# Controller_Sheet.net
KiCad netlist of a schematic drawn in Altium Designer
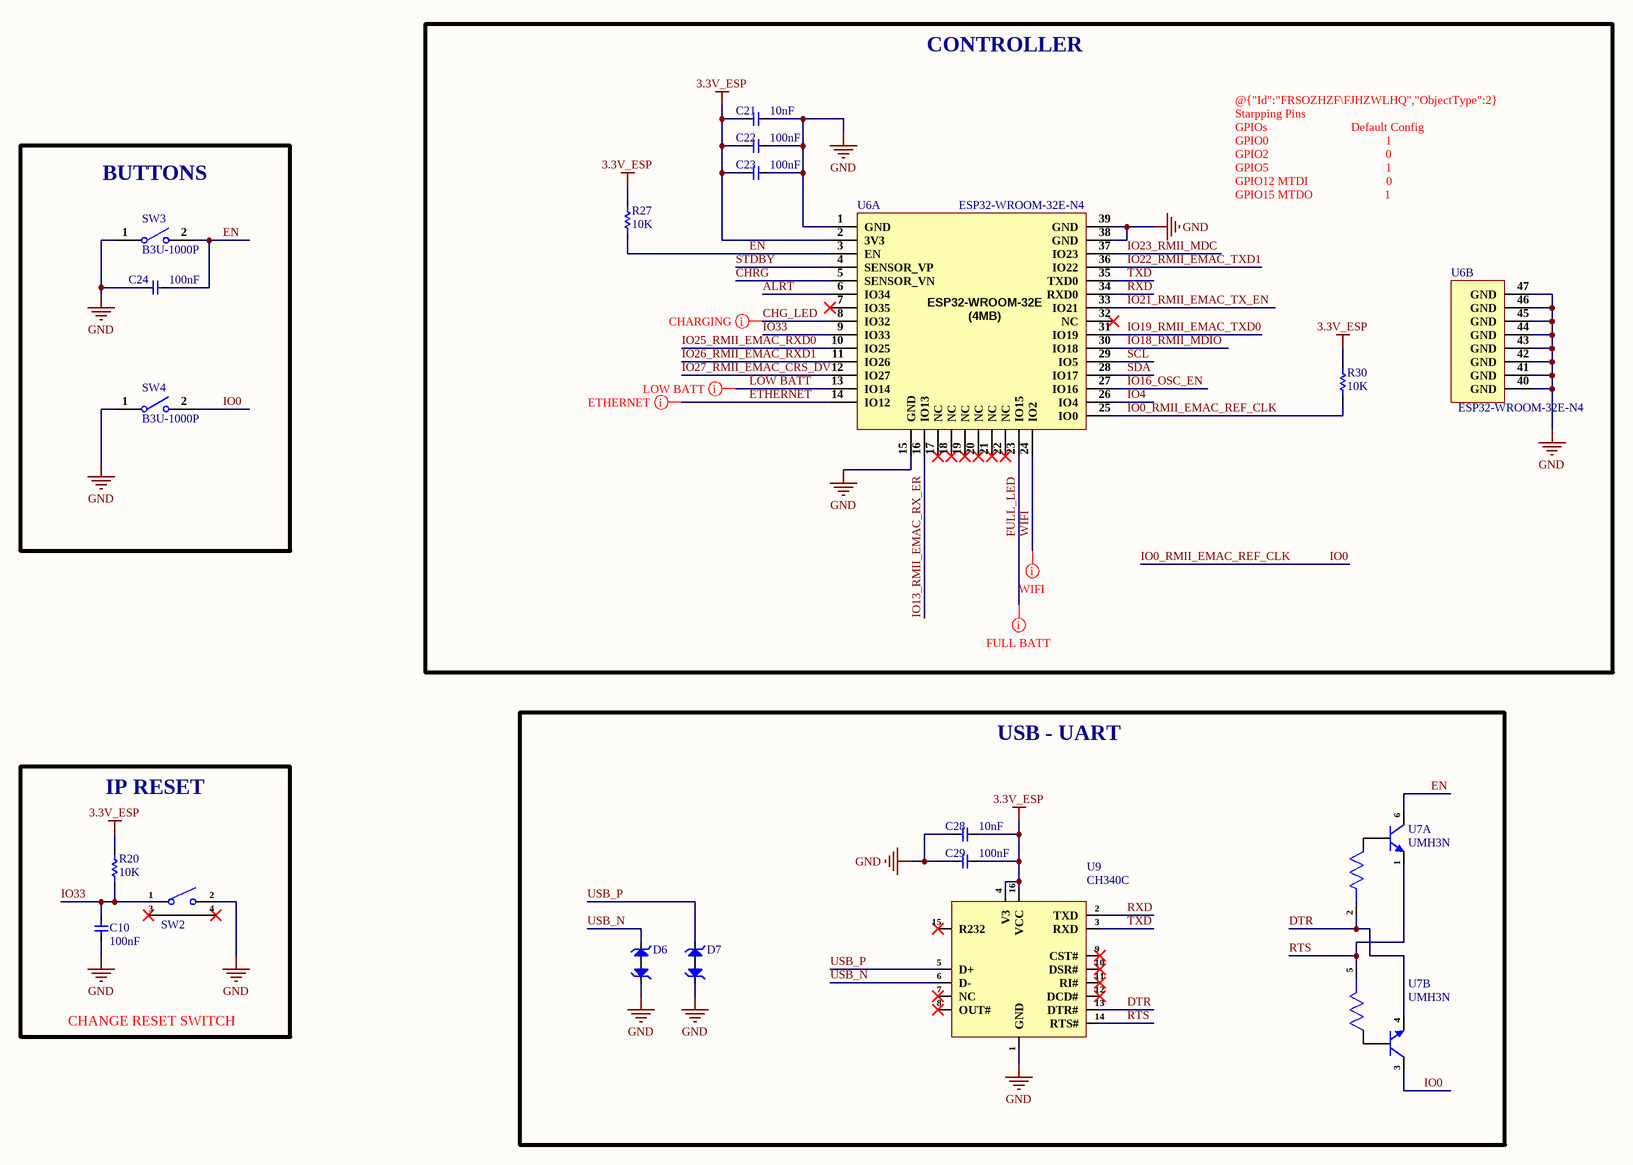
[diagram p0: Controller_Sheet.SchDoc]

(export (version "E")
  (design (tool "Eeschema 10.0.6"))
  (components
    (comp (ref "C10")
      (value "100nF")
      (footprint "cap-0402")
      (description "CAP CER 0.1UF 50V X7R 0402")
      (fields
        (field (name "MANUFACTURER") "TDK")
        (field (name "MANUFACTURER PART NUMBER") "C1005X7R1H104KT000F")
      )
      (libsource (lib "eSpark Libraries") (part "C1005X7R1H104KT000F"))
    )
    (comp (ref "C21")
      (value "10nF")
      (footprint "Cap-0402")
      (description "CAP CER 10000PF 25V X7R 0402")
      (fields
        (field (name "MANUFACTURER") "Yageo")
        (field (name "MANUFACTURER PART NUMBER") "CC0402KRX7R8BB103")
      )
      (libsource (lib "eSpark Libraries") (part "CC0402KRX7R8BB103"))
    )
    (comp (ref "C22")
      (value "100nF")
      (footprint "cap-0402")
      (description "CAP CER 0.1UF 50V X7R 0402")
      (fields
        (field (name "MANUFACTURER") "TDK")
        (field (name "MANUFACTURER PART NUMBER") "C1005X7R1H104KT000F")
      )
      (libsource (lib "eSpark Libraries") (part "C1005X7R1H104KT000F"))
    )
    (comp (ref "C23")
      (value "100nF")
      (footprint "cap-0402")
      (description "CAP CER 0.1UF 50V X7R 0402")
      (fields
        (field (name "MANUFACTURER") "TDK")
        (field (name "MANUFACTURER PART NUMBER") "C1005X7R1H104KT000F")
      )
      (libsource (lib "eSpark Libraries") (part "C1005X7R1H104KT000F"))
    )
    (comp (ref "C24")
      (value "100nF")
      (footprint "cap-0402")
      (description "CAP CER 0.1UF 50V X7R 0402")
      (fields
        (field (name "MANUFACTURER") "TDK")
        (field (name "MANUFACTURER PART NUMBER") "C1005X7R1H104KT000F")
      )
      (libsource (lib "eSpark Libraries") (part "C1005X7R1H104KT000F"))
    )
    (comp (ref "C28")
      (value "10nF")
      (footprint "Cap-0402")
      (description "CAP CER 10000PF 25V X7R 0402")
      (fields
        (field (name "MANUFACTURER") "Yageo")
        (field (name "MANUFACTURER PART NUMBER") "CC0402KRX7R8BB103")
      )
      (libsource (lib "eSpark Libraries") (part "CC0402KRX7R8BB103"))
    )
    (comp (ref "C29")
      (value "100nF")
      (footprint "cap-0402")
      (description "CAP CER 0.1UF 50V X7R 0402")
      (fields
        (field (name "MANUFACTURER") "TDK")
        (field (name "MANUFACTURER PART NUMBER") "C1005X7R1H104KT000F")
      )
      (libsource (lib "eSpark Libraries") (part "C1005X7R1H104KT000F"))
    )
    (comp (ref "D6")
      (value "PESD5V0H1BSFYL")
      (footprint "DSN0603-2")
      (description "TVS DIODE 5VWM 6.3VC DSN0603-2")
      (fields (field (name "MANUFACTURER") "Nexperia") (field (name "LCSC PART NUMBER") "C477989"))
      (libsource (lib "eSpark Libraries") (part "PESD5V0H1BSFYL"))
    )
    (comp (ref "D7")
      (value "PESD5V0H1BSFYL")
      (footprint "DSN0603-2")
      (description "TVS DIODE 5VWM 6.3VC DSN0603-2")
      (fields (field (name "MANUFACTURER") "Nexperia") (field (name "LCSC PART NUMBER") "C477989"))
      (libsource (lib "eSpark Libraries") (part "PESD5V0H1BSFYL"))
    )
    (comp (ref "R20")
      (value "10K")
      (footprint "Res-0402")
      (description "RES 10K OHM 1% 1/16W 0402")
      (fields
        (field (name "MANUFACTURER") "Yageo")
        (field (name "MANUFACTURER PART NUMBER") "RC0402FR-0710KL")
      )
      (libsource (lib "eSpark Libraries") (part "RC0402FR-0710KL"))
    )
    (comp (ref "R27")
      (value "10K")
      (footprint "Res-0402")
      (description "RES 10K OHM 1% 1/16W 0402")
      (fields
        (field (name "MANUFACTURER") "Yageo")
        (field (name "MANUFACTURER PART NUMBER") "RC0402FR-0710KL")
      )
      (libsource (lib "eSpark Libraries") (part "RC0402FR-0710KL"))
    )
    (comp (ref "R30")
      (value "10K")
      (footprint "Res-0402")
      (description "RES 10K OHM 1% 1/16W 0402")
      (fields
        (field (name "MANUFACTURER") "Yageo")
        (field (name "MANUFACTURER PART NUMBER") "RC0402FR-0710KL")
      )
      (libsource (lib "eSpark Libraries") (part "RC0402FR-0710KL"))
    )
    (comp (ref "SW2")
      (value "1-1825027-4")
      (footprint "1-1825027-4")
      (fields (field (name "MANUFACTURER") "TE Connectivity") (field (name "LCSC PART NUMBER") "C2928195"))
      (libsource (lib "eSpark Libraries") (part "1-1825027-4"))
    )
    (comp (ref "SW3")
      (value "B3U-1000P")
      (footprint "B3U-1000P")
      (description "SWITCH TACTILE SPST-NO 0.05A 12V")
      (fields (field (name "MANUFACTURER") "Omron") (field (name "LCSC PART NUMBER") "C231329"))
      (libsource (lib "eSpark Libraries") (part "B3U-1000P"))
    )
    (comp (ref "SW4")
      (value "B3U-1000P")
      (footprint "B3U-1000P")
      (description "SWITCH TACTILE SPST-NO 0.05A 12V")
      (fields (field (name "MANUFACTURER") "Omron") (field (name "LCSC PART NUMBER") "C231329"))
      (libsource (lib "eSpark Libraries") (part "B3U-1000P"))
    )
    (comp (ref "U6")
      (value "ESP32-WROOM-32E-N4")
      (footprint "38-SMD Module")
      (description "RX TXRX MOD WIFI TRACE ANT SMD")
      (fields (field (name "MANUFACTURER") "Espressif Systems") (field (name "LCSC PART NUMBER") "C701341"))
      (libsource (lib "eSpark Libraries") (part "ESP32-WROOM-32E-N4"))
    )
    (comp (ref "U7")
      (value "UMH3N")
      (footprint "SC-70-6_")
      (description "2 NPN pre-biased (Dual) 150mW 100mA 50V SC-70-6(SOT-363) Digital Transistors ROHS")
      (fields (field (name "MANUFACTURER") "Changjiang") (field (name "LCSC PART NUMBER") "C62892"))
      (libsource (lib "eSpark Libraries") (part "UMH3N"))
    )
    (comp (ref "U9")
      (value "CH340C")
      (footprint "SOP-16")
      (description "2Mbps Transceiver USB 2.0 SOP-16 USB ICs ROHS")
      (fields (field (name "MANUFACTURER") "WCH") (field (name "LCSC PART NUMBER") "C84681"))
      (libsource (lib "eSpark Libraries") (part "CH340C"))
    )
  )
  (nets
    (net (code "1") (name "/ALRT") (class "Default")
      (node (ref "U6") (pin "6") (pinfunction "IO34_6") (pintype "passive"))
    )
    (net (code "2") (name "/CHG_LED") (class "Default")
      (node (ref "U6") (pin "8") (pinfunction "IO32_8") (pintype "passive"))
    )
    (net (code "3") (name "/CHRG") (class "Default")
      (node (ref "U6") (pin "5") (pinfunction "SENSOR_VN_5") (pintype "passive"))
    )
    (net (code "4") (name "/DTR") (class "Default")
      (node (ref "U7") (pin "2") (pintype "passive"))
      (node (ref "U7") (pin "4") (pinfunction "E_4") (pintype "passive"))
      (node (ref "U9") (pin "13") (pinfunction "DTR#_13") (pintype "passive"))
    )
    (net (code "5") (name "/EN") (class "Default")
      (node (ref "C24") (pin "1") (pinfunction "1_1") (pintype "passive"))
      (node (ref "R27") (pin "1") (pinfunction "1_1") (pintype "passive"))
      (node (ref "SW3") (pin "2") (pinfunction "2_2") (pintype "passive"))
      (node (ref "U6") (pin "3") (pinfunction "EN_3") (pintype "passive"))
      (node (ref "U7") (pin "6") (pinfunction "C_6") (pintype "passive"))
    )
    (net (code "6") (name "/ETHERNET") (class "Default")
      (node (ref "U6") (pin "14") (pinfunction "IO12_14") (pintype "passive"))
    )
    (net (code "7") (name "/FULL_LED") (class "Default")
      (node (ref "U6") (pin "23") (pinfunction "IO15_23") (pintype "passive"))
    )
    (net (code "8") (name "/IO0") (class "Default")
      (node (ref "R30") (pin "1") (pinfunction "1_1") (pintype "passive"))
      (node (ref "SW4") (pin "2") (pinfunction "2_2") (pintype "passive"))
      (node (ref "U6") (pin "25") (pinfunction "IO0_25") (pintype "passive"))
      (node (ref "U7") (pin "3") (pinfunction "C_3") (pintype "passive"))
    )
    (net (code "9") (name "/IO4") (class "Default")
      (node (ref "U6") (pin "26") (pinfunction "IO4_26") (pintype "passive"))
    )
    (net (code "10") (name "/IO13_RMII_EMAC_RX_ER") (class "Default")
      (node (ref "U6") (pin "16") (pinfunction "IO13_16") (pintype "passive"))
    )
    (net (code "11") (name "/IO16_OSC_EN") (class "Default")
      (node (ref "U6") (pin "27") (pinfunction "IO16_27") (pintype "passive"))
    )
    (net (code "12") (name "/IO18_RMII_MDIO") (class "Default")
      (node (ref "U6") (pin "30") (pinfunction "IO18_30") (pintype "passive"))
    )
    (net (code "13") (name "/IO19_RMII_EMAC_TXD0") (class "Default")
      (node (ref "U6") (pin "31") (pinfunction "IO19_31") (pintype "passive"))
    )
    (net (code "14") (name "/IO21_RMII_EMAC_TX_EN") (class "Default")
      (node (ref "U6") (pin "33") (pinfunction "IO21_33") (pintype "passive"))
    )
    (net (code "15") (name "/IO22_RMII_EMAC_TXD1") (class "Default")
      (node (ref "U6") (pin "36") (pinfunction "IO22_36") (pintype "passive"))
    )
    (net (code "16") (name "/IO23_RMII_MDC") (class "Default")
      (node (ref "U6") (pin "37") (pinfunction "IO23_37") (pintype "passive"))
    )
    (net (code "17") (name "/IO25_RMII_EMAC_RXD0") (class "Default")
      (node (ref "U6") (pin "10") (pinfunction "IO25_10") (pintype "passive"))
    )
    (net (code "18") (name "/IO26_RMII_EMAC_RXD1") (class "Default")
      (node (ref "U6") (pin "11") (pinfunction "IO26_11") (pintype "passive"))
    )
    (net (code "19") (name "/IO27_RMII_EMAC_CRS_DV") (class "Default")
      (node (ref "U6") (pin "12") (pinfunction "IO27_12") (pintype "passive"))
    )
    (net (code "20") (name "/IO33") (class "Default")
      (node (ref "C10") (pin "1") (pinfunction "1_1") (pintype "passive"))
      (node (ref "R20") (pin "1") (pinfunction "1_1") (pintype "passive"))
      (node (ref "SW2") (pin "1") (pinfunction "2_1") (pintype "passive"))
      (node (ref "U6") (pin "9") (pinfunction "IO33_9") (pintype "passive"))
    )
    (net (code "21") (name "/LOW BATT") (class "Default")
      (node (ref "U6") (pin "13") (pinfunction "IO14_13") (pintype "passive"))
    )
    (net (code "22") (name "/RTS") (class "Default")
      (node (ref "U7") (pin "1") (pinfunction "E_1") (pintype "passive"))
      (node (ref "U7") (pin "5") (pintype "passive"))
      (node (ref "U9") (pin "14") (pinfunction "RTS#_14") (pintype "passive"))
    )
    (net (code "23") (name "/RXD") (class "Default")
      (node (ref "U6") (pin "34") (pinfunction "RXD0_34") (pintype "passive"))
      (node (ref "U9") (pin "2") (pinfunction "TXD_2") (pintype "passive"))
    )
    (net (code "24") (name "/SCL") (class "Default")
      (node (ref "U6") (pin "29") (pinfunction "IO5_29") (pintype "passive"))
    )
    (net (code "25") (name "/SDA") (class "Default")
      (node (ref "U6") (pin "28") (pinfunction "IO17_28") (pintype "passive"))
    )
    (net (code "26") (name "/STDBY") (class "Default")
      (node (ref "U6") (pin "4") (pinfunction "SENSOR_VP_4") (pintype "passive"))
    )
    (net (code "27") (name "/TXD") (class "Default")
      (node (ref "U6") (pin "35") (pinfunction "TXD0_35") (pintype "passive"))
      (node (ref "U9") (pin "3") (pinfunction "RXD_3") (pintype "passive"))
    )
    (net (code "28") (name "/USB_N") (class "Default")
      (node (ref "D6") (pin "2") (pinfunction "2_2") (pintype "passive"))
      (node (ref "U9") (pin "6") (pinfunction "D-_6") (pintype "passive"))
    )
    (net (code "29") (name "/USB_P") (class "Default")
      (node (ref "D7") (pin "2") (pinfunction "2_2") (pintype "passive"))
      (node (ref "U9") (pin "5") (pinfunction "D+_5") (pintype "passive"))
    )
    (net (code "30") (name "/WIFI") (class "Default")
      (node (ref "U6") (pin "24") (pinfunction "IO2_24") (pintype "passive"))
    )
    (net (code "31") (name "3.3V_ESP") (class "Default")
      (node (ref "C21") (pin "2") (pinfunction "2_2") (pintype "passive"))
      (node (ref "C22") (pin "2") (pinfunction "2_2") (pintype "passive"))
      (node (ref "C23") (pin "2") (pinfunction "2_2") (pintype "passive"))
      (node (ref "C28") (pin "1") (pinfunction "1_1") (pintype "passive"))
      (node (ref "C29") (pin "1") (pinfunction "1_1") (pintype "passive"))
      (node (ref "R20") (pin "2") (pinfunction "2_2") (pintype "passive"))
      (node (ref "R27") (pin "2") (pinfunction "2_2") (pintype "passive"))
      (node (ref "R30") (pin "2") (pinfunction "2_2") (pintype "passive"))
      (node (ref "U6") (pin "2") (pinfunction "3V3_2") (pintype "passive"))
      (node (ref "U9") (pin "16") (pinfunction "VCC_16") (pintype "passive"))
      (node (ref "U9") (pin "4") (pinfunction "V3_4") (pintype "passive"))
    )
    (net (code "32") (name "GND") (class "Default")
      (node (ref "C10") (pin "2") (pinfunction "2_2") (pintype "passive"))
      (node (ref "C21") (pin "1") (pinfunction "1_1") (pintype "passive"))
      (node (ref "C22") (pin "1") (pinfunction "1_1") (pintype "passive"))
      (node (ref "C23") (pin "1") (pinfunction "1_1") (pintype "passive"))
      (node (ref "C24") (pin "2") (pinfunction "2_2") (pintype "passive"))
      (node (ref "C28") (pin "2") (pinfunction "2_2") (pintype "passive"))
      (node (ref "C29") (pin "2") (pinfunction "2_2") (pintype "passive"))
      (node (ref "D6") (pin "1") (pinfunction "1_1") (pintype "passive"))
      (node (ref "D7") (pin "1") (pinfunction "1_1") (pintype "passive"))
      (node (ref "SW2") (pin "2") (pinfunction "2_2") (pintype "passive"))
      (node (ref "SW3") (pin "1") (pinfunction "1_1") (pintype "passive"))
      (node (ref "SW4") (pin "1") (pinfunction "1_1") (pintype "passive"))
      (node (ref "U6") (pin "1") (pinfunction "GND_1") (pintype "passive"))
      (node (ref "U6") (pin "15") (pinfunction "GND_15") (pintype "passive"))
      (node (ref "U6") (pin "38") (pinfunction "GND_38") (pintype "passive"))
      (node (ref "U6") (pin "39") (pinfunction "GND_39") (pintype "passive"))
      (node (ref "U6") (pin "40") (pinfunction "GND_40") (pintype "passive"))
      (node (ref "U6") (pin "41") (pinfunction "GND_41") (pintype "passive"))
      (node (ref "U6") (pin "42") (pinfunction "GND_42") (pintype "passive"))
      (node (ref "U6") (pin "43") (pinfunction "GND_43") (pintype "passive"))
      (node (ref "U6") (pin "44") (pinfunction "GND_44") (pintype "passive"))
      (node (ref "U6") (pin "45") (pinfunction "GND_45") (pintype "passive"))
      (node (ref "U6") (pin "46") (pinfunction "GND_46") (pintype "passive"))
      (node (ref "U6") (pin "47") (pinfunction "GND_47") (pintype "passive"))
      (node (ref "U9") (pin "1") (pinfunction "GND_1") (pintype "passive"))
    )
    (net (code "33") (name "unconnected-(SW2-Pad3)") (class "Default")
      (node (ref "SW2") (pin "3") (pinfunction "3_3") (pintype "passive+no_connect"))
    )
    (net (code "34") (name "unconnected-(SW2-Pad4)") (class "Default")
      (node (ref "SW2") (pin "4") (pinfunction "4_4") (pintype "passive+no_connect"))
    )
    (net (code "35") (name "unconnected-(U6A-IO35-Pad7)") (class "Default")
      (node (ref "U6") (pin "7") (pinfunction "IO35_7") (pintype "passive+no_connect"))
    )
    (net (code "36") (name "unconnected-(U6A-NC-Pad17)") (class "Default")
      (node (ref "U6") (pin "17") (pinfunction "NC_17") (pintype "passive+no_connect"))
    )
    (net (code "37") (name "unconnected-(U6A-NC-Pad18)") (class "Default")
      (node (ref "U6") (pin "18") (pinfunction "NC_18") (pintype "passive+no_connect"))
    )
    (net (code "38") (name "unconnected-(U6A-NC-Pad19)") (class "Default")
      (node (ref "U6") (pin "19") (pinfunction "NC_19") (pintype "passive+no_connect"))
    )
    (net (code "39") (name "unconnected-(U6A-NC-Pad20)") (class "Default")
      (node (ref "U6") (pin "20") (pinfunction "NC_20") (pintype "passive+no_connect"))
    )
    (net (code "40") (name "unconnected-(U6A-NC-Pad21)") (class "Default")
      (node (ref "U6") (pin "21") (pinfunction "NC_21") (pintype "passive+no_connect"))
    )
    (net (code "41") (name "unconnected-(U6A-NC-Pad22)") (class "Default")
      (node (ref "U6") (pin "22") (pinfunction "NC_22") (pintype "passive+no_connect"))
    )
    (net (code "42") (name "unconnected-(U6A-NC-Pad32)") (class "Default")
      (node (ref "U6") (pin "32") (pinfunction "NC_32") (pintype "passive+no_connect"))
    )
    (net (code "43") (name "unconnected-(U9-CST#-Pad9)") (class "Default")
      (node (ref "U9") (pin "9") (pinfunction "CST#_9") (pintype "passive+no_connect"))
    )
    (net (code "44") (name "unconnected-(U9-DCD#-Pad12)") (class "Default")
      (node (ref "U9") (pin "12") (pinfunction "DCD#_12") (pintype "passive+no_connect"))
    )
    (net (code "45") (name "unconnected-(U9-DSR#-Pad10)") (class "Default")
      (node (ref "U9") (pin "10") (pinfunction "DSR#_10") (pintype "passive+no_connect"))
    )
    (net (code "46") (name "unconnected-(U9-NC-Pad7)") (class "Default")
      (node (ref "U9") (pin "7") (pinfunction "NC_7") (pintype "passive+no_connect"))
    )
    (net (code "47") (name "unconnected-(U9-OUT#-Pad8)") (class "Default")
      (node (ref "U9") (pin "8") (pinfunction "OUT#_8") (pintype "passive+no_connect"))
    )
    (net (code "48") (name "unconnected-(U9-R232-Pad15)") (class "Default")
      (node (ref "U9") (pin "15") (pinfunction "R232_15") (pintype "passive+no_connect"))
    )
    (net (code "49") (name "unconnected-(U9-RI#-Pad11)") (class "Default")
      (node (ref "U9") (pin "11") (pinfunction "RI#_11") (pintype "passive+no_connect"))
    )
  )
)
